# CoreCtrl.net
KiCad netlist of a schematic drawn in Altium Designer
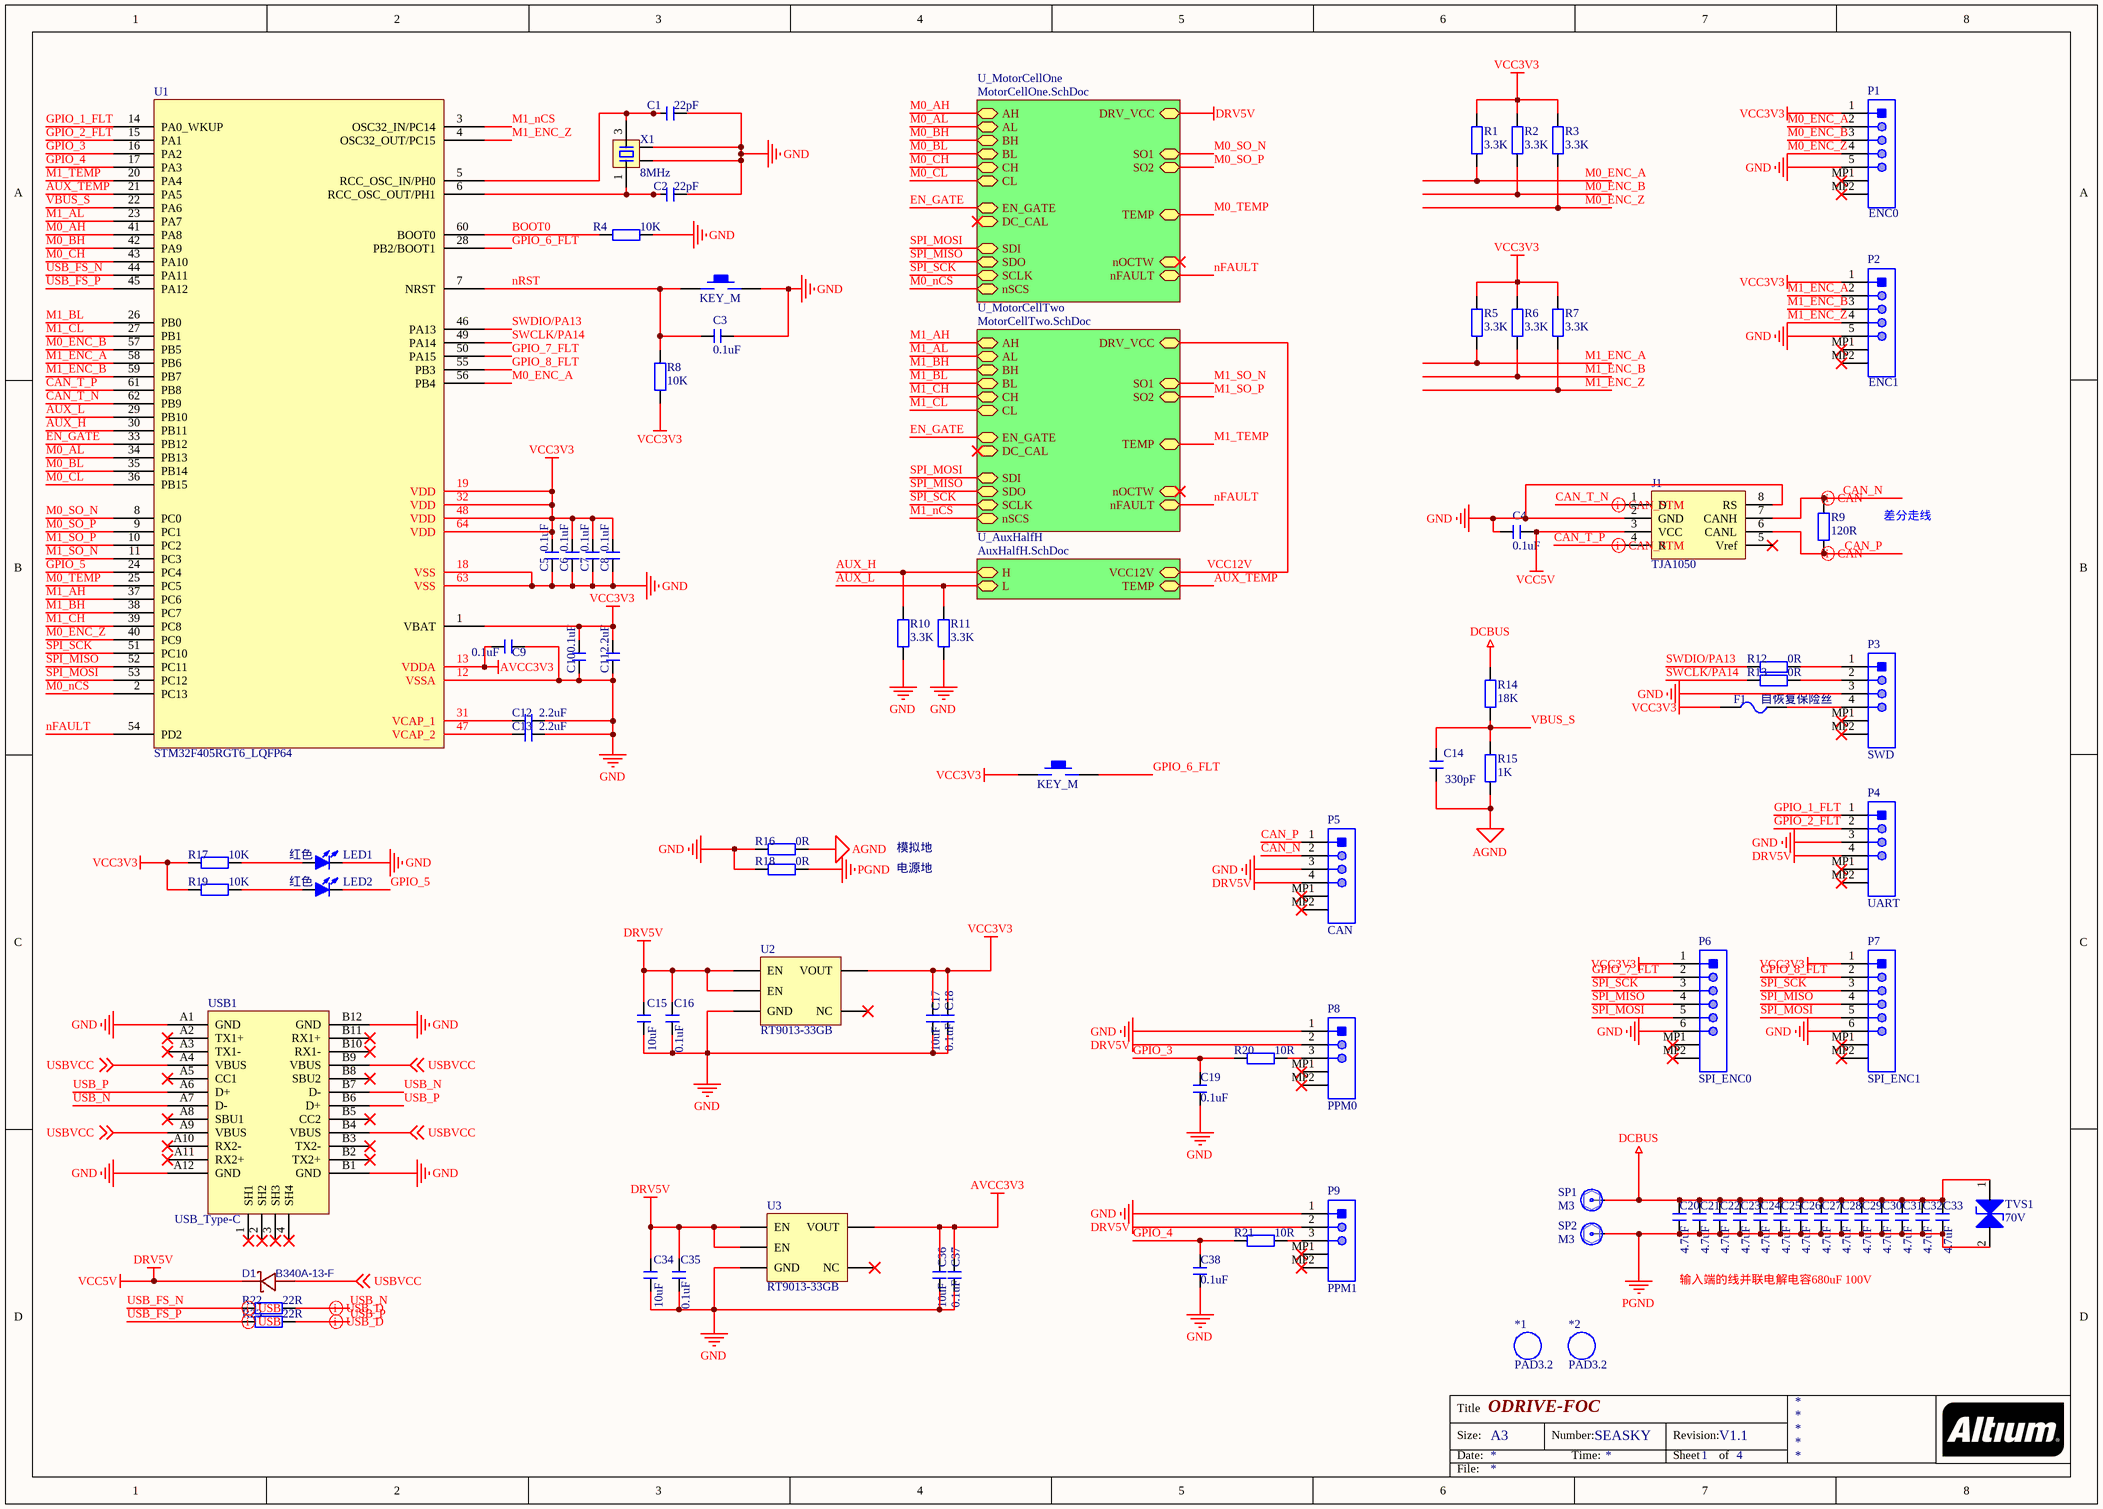
[diagram p0: CoreCtrl.SchDoc]

(export (version "E")
  (design (tool "Eeschema 10.0.6"))
  (components
    (comp (ref "*1") (value "PAD3.2") (footprint "PAD3.2") (libsource (lib "mx_pcb_library") (part "PAD3.2")))
    (comp (ref "*2") (value "PAD3.2") (footprint "PAD3.2") (libsource (lib "mx_pcb_library") (part "PAD3.2")))
    (comp (ref "C1")
      (value "22pF")
      (footprint "C 0603_L")
      (description "贴片电容")
      (libsource (lib "0.1 - 电阻-电容-电感") (part "C"))
    )
    (comp (ref "C2")
      (value "22pF")
      (footprint "C 0603_L")
      (description "贴片电容")
      (libsource (lib "0.1 - 电阻-电容-电感") (part "C"))
    )
    (comp (ref "C3")
      (value "0.1uF")
      (footprint "C 0603_L")
      (description "贴片电容")
      (libsource (lib "0.1 - 电阻-电容-电感") (part "C"))
    )
    (comp (ref "C4")
      (value "0.1uF")
      (footprint "C 0603_L")
      (description "贴片电容")
      (libsource (lib "0.1 - 电阻-电容-电感") (part "C"))
    )
    (comp (ref "C5")
      (value "0.1uF")
      (footprint "C 0603_L")
      (description "贴片电容")
      (libsource (lib "0.1 - 电阻-电容-电感") (part "C"))
    )
    (comp (ref "C6")
      (value "0.1uF")
      (footprint "C 0603_L")
      (description "贴片电容")
      (libsource (lib "0.1 - 电阻-电容-电感") (part "C"))
    )
    (comp (ref "C7")
      (value "0.1uF")
      (footprint "C 0603_L")
      (description "贴片电容")
      (libsource (lib "0.1 - 电阻-电容-电感") (part "C"))
    )
    (comp (ref "C8")
      (value "0.1uF")
      (footprint "C 0603_L")
      (description "贴片电容")
      (libsource (lib "0.1 - 电阻-电容-电感") (part "C"))
    )
    (comp (ref "C9")
      (value "0.1uF")
      (footprint "C 0603_L")
      (description "贴片电容")
      (libsource (lib "0.1 - 电阻-电容-电感") (part "C"))
    )
    (comp (ref "C10")
      (value "0.1uF")
      (footprint "C 0603_L")
      (description "贴片电容")
      (libsource (lib "0.1 - 电阻-电容-电感") (part "C"))
    )
    (comp (ref "C11")
      (value "2.2uF")
      (footprint "C 0603_L")
      (description "贴片电容")
      (libsource (lib "0.1 - 电阻-电容-电感") (part "C"))
    )
    (comp (ref "C12")
      (value "2.2uF")
      (footprint "C 0603_L")
      (description "贴片电容")
      (libsource (lib "0.1 - 电阻-电容-电感") (part "C"))
    )
    (comp (ref "C13")
      (value "2.2uF")
      (footprint "C 0603_L")
      (description "贴片电容")
      (libsource (lib "0.1 - 电阻-电容-电感") (part "C"))
    )
    (comp (ref "C14")
      (value "330pF")
      (footprint "C 0603_L")
      (description "贴片电容")
      (libsource (lib "0.1 - 电阻-电容-电感") (part "C"))
    )
    (comp (ref "C15")
      (value "10uF")
      (footprint "C 0805_L")
      (description "贴片电容")
      (libsource (lib "0.1 - 电阻-电容-电感") (part "C"))
    )
    (comp (ref "C16")
      (value "0.1uF")
      (footprint "C 0805_L")
      (description "贴片电容")
      (libsource (lib "0.1 - 电阻-电容-电感") (part "C"))
    )
    (comp (ref "C17")
      (value "10uF")
      (footprint "C 0805_L")
      (description "贴片电容")
      (libsource (lib "0.1 - 电阻-电容-电感") (part "C"))
    )
    (comp (ref "C18")
      (value "0.1uF")
      (footprint "C 0805_L")
      (description "贴片电容")
      (libsource (lib "0.1 - 电阻-电容-电感") (part "C"))
    )
    (comp (ref "C19")
      (value "0.1uF")
      (footprint "C 0603_L")
      (description "贴片电容")
      (libsource (lib "0.1 - 电阻-电容-电感") (part "C"))
    )
    (comp (ref "C20")
      (value "4.7uF")
      (footprint "C 1210_L")
      (description "贴片电容")
      (libsource (lib "0.1 - 电阻-电容-电感") (part "C"))
    )
    (comp (ref "C21")
      (value "4.7uF")
      (footprint "C 1210_L")
      (description "贴片电容")
      (libsource (lib "0.1 - 电阻-电容-电感") (part "C"))
    )
    (comp (ref "C22")
      (value "4.7uF")
      (footprint "C 1210_L")
      (description "贴片电容")
      (libsource (lib "0.1 - 电阻-电容-电感") (part "C"))
    )
    (comp (ref "C23")
      (value "4.7uF")
      (footprint "C 1210_L")
      (description "贴片电容")
      (libsource (lib "0.1 - 电阻-电容-电感") (part "C"))
    )
    (comp (ref "C24")
      (value "4.7uF")
      (footprint "C 1210_L")
      (description "贴片电容")
      (libsource (lib "0.1 - 电阻-电容-电感") (part "C"))
    )
    (comp (ref "C25")
      (value "4.7uF")
      (footprint "C 1210_L")
      (description "贴片电容")
      (libsource (lib "0.1 - 电阻-电容-电感") (part "C"))
    )
    (comp (ref "C26")
      (value "4.7uF")
      (footprint "C 1210_L")
      (description "贴片电容")
      (libsource (lib "0.1 - 电阻-电容-电感") (part "C"))
    )
    (comp (ref "C27")
      (value "4.7uF")
      (footprint "C 1210_L")
      (description "贴片电容")
      (libsource (lib "0.1 - 电阻-电容-电感") (part "C"))
    )
    (comp (ref "C28")
      (value "4.7uF")
      (footprint "C 1210_L")
      (description "贴片电容")
      (libsource (lib "0.1 - 电阻-电容-电感") (part "C"))
    )
    (comp (ref "C29")
      (value "4.7uF")
      (footprint "C 1210_L")
      (description "贴片电容")
      (libsource (lib "0.1 - 电阻-电容-电感") (part "C"))
    )
    (comp (ref "C30")
      (value "4.7uF")
      (footprint "C 1210_L")
      (description "贴片电容")
      (libsource (lib "0.1 - 电阻-电容-电感") (part "C"))
    )
    (comp (ref "C31")
      (value "4.7uF")
      (footprint "C 1210_L")
      (description "贴片电容")
      (libsource (lib "0.1 - 电阻-电容-电感") (part "C"))
    )
    (comp (ref "C32")
      (value "4.7uF")
      (footprint "C 1210_L")
      (description "贴片电容")
      (libsource (lib "0.1 - 电阻-电容-电感") (part "C"))
    )
    (comp (ref "C33")
      (value "4.7uF")
      (footprint "C 1210_L")
      (description "贴片电容")
      (libsource (lib "0.1 - 电阻-电容-电感") (part "C"))
    )
    (comp (ref "C34")
      (value "10uF")
      (footprint "C 0805_L")
      (description "贴片电容")
      (libsource (lib "0.1 - 电阻-电容-电感") (part "C"))
    )
    (comp (ref "C35")
      (value "0.1uF")
      (footprint "C 0805_L")
      (description "贴片电容")
      (libsource (lib "0.1 - 电阻-电容-电感") (part "C"))
    )
    (comp (ref "C36")
      (value "10uF")
      (footprint "C 0805_L")
      (description "贴片电容")
      (libsource (lib "0.1 - 电阻-电容-电感") (part "C"))
    )
    (comp (ref "C37")
      (value "0.1uF")
      (footprint "C 0805_L")
      (description "贴片电容")
      (libsource (lib "0.1 - 电阻-电容-电感") (part "C"))
    )
    (comp (ref "C38")
      (value "0.1uF")
      (footprint "C 0603_L")
      (description "贴片电容")
      (libsource (lib "0.1 - 电阻-电容-电感") (part "C"))
    )
    (comp (ref "D1")
      (value "B340A-13-F")
      (footprint "SMA_L4.4-W2.6-LS5.0-RD")
      (fields (field (name "BOM_SUPPLIER PART") "C85098"))
      (libsource (lib "mx_pcb_library") (part "B340A-13-F"))
    )
    (comp (ref "F1")
      (value "自恢复保险丝")
      (footprint "FU 0603")
      (description "贴片保险丝")
      (libsource (lib "2.0 - 保险丝-晶振-光耦") (part "FU"))
    )
    (comp (ref "J1")
      (value "TJA1050")
      (footprint "SOIC-8_150mil")
      (description "CAN芯片")
      (libsource (lib "mx_pcb_library") (part "TJA1050"))
    )
    (comp (ref "LED1")
      (value "红色")
      (footprint "LED 0805G")
      (description "贴片LED")
      (libsource (lib "0.3 - LED发光二极管") (part "LED-SMD"))
    )
    (comp (ref "LED2")
      (value "红色")
      (footprint "LED 0805G")
      (description "贴片LED")
      (libsource (lib "0.3 - LED发光二极管") (part "LED-SMD"))
    )
    (comp (ref "P1")
      (value "ENC0")
      (footprint "JST-SM05B-GHS-TB_V")
      (fields (field (name "MANUFACTURER") "JST"))
      (libsource (lib "JST GH connector") (part "SM05B-GHS-TB(LF)(SN)"))
    )
    (comp (ref "P2")
      (value "ENC1")
      (footprint "JST-SM05B-GHS-TB_V")
      (fields (field (name "MANUFACTURER") "JST"))
      (libsource (lib "JST GH connector") (part "SM05B-GHS-TB(LF)(SN)"))
    )
    (comp (ref "P3")
      (value "SWD")
      (footprint "JST-SM04B-GHS-TB_V")
      (fields (field (name "MANUFACTURER") "JST"))
      (libsource (lib "JST GH connector") (part "SM04B-GHS-TB(LF)(SN)"))
    )
    (comp (ref "P4")
      (value "UART")
      (footprint "JST-SM04B-GHS-TB_V")
      (fields (field (name "MANUFACTURER") "JST"))
      (libsource (lib "JST GH connector") (part "SM04B-GHS-TB(LF)(SN)"))
    )
    (comp (ref "P5")
      (value "CAN")
      (footprint "JST-SM04B-GHS-TB_V")
      (fields (field (name "MANUFACTURER") "JST"))
      (libsource (lib "JST GH connector") (part "SM04B-GHS-TB(LF)(SN)"))
    )
    (comp (ref "P6")
      (value "SPI_ENC0")
      (footprint "JST-SM06B-GHS-TB_V")
      (fields (field (name "MANUFACTURER") "JST"))
      (libsource (lib "JST GH connector") (part "SM06B-GHS-TB(LF)(SN)"))
    )
    (comp (ref "P7")
      (value "SPI_ENC1")
      (footprint "JST-BM06B-GHS-TBT_V")
      (fields (field (name "MANUFACTURER") "JST"))
      (libsource (lib "JST GH connector") (part "BM06B-GHS-TBT(LF)(SN)"))
    )
    (comp (ref "P8")
      (value "PPM0")
      (footprint "JST-SM03B-GHS-TB_V")
      (fields (field (name "MANUFACTURER") "JST"))
      (libsource (lib "JST GH connector") (part "SM03B-GHS-TB(LF)(SN)"))
    )
    (comp (ref "P9")
      (value "PPM1")
      (footprint "JST-SM03B-GHS-TB_V")
      (fields (field (name "MANUFACTURER") "JST"))
      (libsource (lib "JST GH connector") (part "SM03B-GHS-TB(LF)(SN)"))
    )
    (comp (ref "R1")
      (value "3.3K")
      (footprint "R 0603_L")
      (description "贴片电阻")
      (libsource (lib "0.1 - 电阻-电容-电感") (part "R"))
    )
    (comp (ref "R2")
      (value "3.3K")
      (footprint "R 0603_L")
      (description "贴片电阻")
      (libsource (lib "0.1 - 电阻-电容-电感") (part "R"))
    )
    (comp (ref "R3")
      (value "3.3K")
      (footprint "R 0603_L")
      (description "贴片电阻")
      (libsource (lib "0.1 - 电阻-电容-电感") (part "R"))
    )
    (comp (ref "R4")
      (value "10K")
      (footprint "R 0603_L")
      (description "贴片电阻")
      (libsource (lib "0.1 - 电阻-电容-电感") (part "R"))
    )
    (comp (ref "R5")
      (value "3.3K")
      (footprint "R 0603_L")
      (description "贴片电阻")
      (libsource (lib "0.1 - 电阻-电容-电感") (part "R"))
    )
    (comp (ref "R6")
      (value "3.3K")
      (footprint "R 0603_L")
      (description "贴片电阻")
      (libsource (lib "0.1 - 电阻-电容-电感") (part "R"))
    )
    (comp (ref "R7")
      (value "3.3K")
      (footprint "R 0603_L")
      (description "贴片电阻")
      (libsource (lib "0.1 - 电阻-电容-电感") (part "R"))
    )
    (comp (ref "R8")
      (value "10K")
      (footprint "R 0603_L")
      (description "贴片电阻")
      (libsource (lib "0.1 - 电阻-电容-电感") (part "R"))
    )
    (comp (ref "R9")
      (value "120R")
      (footprint "R 0603_L")
      (description "贴片电阻")
      (libsource (lib "0.1 - 电阻-电容-电感") (part "R"))
    )
    (comp (ref "R10")
      (value "3.3K")
      (footprint "R 0603_L")
      (description "贴片电阻")
      (libsource (lib "0.1 - 电阻-电容-电感") (part "R"))
    )
    (comp (ref "R11")
      (value "3.3K")
      (footprint "R 0603_L")
      (description "贴片电阻")
      (libsource (lib "0.1 - 电阻-电容-电感") (part "R"))
    )
    (comp (ref "R12")
      (value "0R")
      (footprint "R 0603_L")
      (description "贴片电阻")
      (libsource (lib "0.1 - 电阻-电容-电感") (part "R"))
    )
    (comp (ref "R13")
      (value "0R")
      (footprint "R 0603_L")
      (description "贴片电阻")
      (libsource (lib "0.1 - 电阻-电容-电感") (part "R"))
    )
    (comp (ref "R14")
      (value "18K")
      (footprint "R 0603_L")
      (description "贴片电阻")
      (libsource (lib "0.1 - 电阻-电容-电感") (part "R"))
    )
    (comp (ref "R15")
      (value "1K")
      (footprint "R 0603_L")
      (description "贴片电阻")
      (libsource (lib "0.1 - 电阻-电容-电感") (part "R"))
    )
    (comp (ref "R16")
      (value "0R")
      (footprint "R 0603_L")
      (description "贴片电阻")
      (libsource (lib "0.1 - 电阻-电容-电感") (part "R"))
    )
    (comp (ref "R17")
      (value "10K")
      (footprint "R 0603_L")
      (description "贴片电阻")
      (libsource (lib "0.1 - 电阻-电容-电感") (part "R"))
    )
    (comp (ref "R18")
      (value "0R")
      (footprint "R 0603_L")
      (description "贴片电阻")
      (libsource (lib "0.1 - 电阻-电容-电感") (part "R"))
    )
    (comp (ref "R19")
      (value "10K")
      (footprint "R 0603_L")
      (description "贴片电阻")
      (libsource (lib "0.1 - 电阻-电容-电感") (part "R"))
    )
    (comp (ref "R20")
      (value "10R")
      (footprint "R 0603_L")
      (description "贴片电阻")
      (libsource (lib "0.1 - 电阻-电容-电感") (part "R"))
    )
    (comp (ref "R21")
      (value "10R")
      (footprint "R 0603_L")
      (description "贴片电阻")
      (libsource (lib "0.1 - 电阻-电容-电感") (part "R"))
    )
    (comp (ref "R22")
      (value "22R")
      (footprint "R 0603_L")
      (description "贴片电阻")
      (libsource (lib "0.1 - 电阻-电容-电感") (part "R"))
    )
    (comp (ref "R23")
      (value "22R")
      (footprint "R 0603_L")
      (description "贴片电阻")
      (libsource (lib "0.1 - 电阻-电容-电感") (part "R"))
    )
    (comp (ref "RST1")
      (value "KEY_M")
      (footprint "SMD-3.2*4.2")
      (libsource (lib "mx_pcb_library") (part "KEY_M"))
    )
    (comp (ref "RST2")
      (value "KEY_M")
      (footprint "SMD-3.2*4.2")
      (libsource (lib "mx_pcb_library") (part "KEY_M"))
    )
    (comp (ref "SP1")
      (value "M3")
      (footprint "PAD1.5")
      (description "铜柱")
      (libsource (lib "mx_pcb_library") (part "固定焊盘"))
    )
    (comp (ref "SP2")
      (value "M3")
      (footprint "PAD1.5")
      (description "铜柱")
      (libsource (lib "mx_pcb_library") (part "固定焊盘"))
    )
    (comp (ref "TVS1")
      (value "70V")
      (footprint "SMA(DO-214AC)")
      (libsource (lib "mx_pcb_library") (part "SMAJ28CA"))
    )
    (comp (ref "U1")
      (value "STM32F405RGT6_LQFP64")
      (footprint "LQFP-64_10X10X05P")
      (libsource (lib "mx_pcb_library") (part "STM32F405RGT6_LQFP64"))
    )
    (comp (ref "U2")
      (value "RT9013-33GB")
      (footprint "SOT23-5M")
      (libsource (lib "mx_pcb_library") (part "RT9013-33GB"))
    )
    (comp (ref "U3")
      (value "RT9013-33GB")
      (footprint "SOT23-5M")
      (libsource (lib "mx_pcb_library") (part "RT9013-33GB"))
    )
    (comp (ref "USB1")
      (value "USB_Type-C")
      (footprint "Type-C-TOP")
      (libsource (lib "mx_pcb_library") (part "USB_Type-C"))
    )
    (comp (ref "X1")
      (value "8MHz")
      (footprint "OSC 3225-4P")
      (description "4脚无源晶振")
      (libsource (lib "2.0 - 保险丝-晶振-光耦") (part "XTAL-4P"))
    )
  )
  (nets
    (net (code "1") (name "/AUX_H") (class "Default")
      (node (ref "R10") (pin "1") (pinfunction "1_1") (pintype "passive"))
      (node (ref "U1") (pin "30") (pinfunction "PB11_30") (pintype "passive"))
    )
    (net (code "2") (name "/AUX_L") (class "Default")
      (node (ref "R11") (pin "1") (pinfunction "1_1") (pintype "passive"))
      (node (ref "U1") (pin "29") (pinfunction "PB10_29") (pintype "passive"))
    )
    (net (code "3") (name "/AUX_TEMP") (class "Default")
      (node (ref "U1") (pin "21") (pinfunction "PA5_21") (pintype "passive"))
    )
    (net (code "4") (name "/BOOT0") (class "Default")
      (node (ref "R4") (pin "2") (pinfunction "2_2") (pintype "passive"))
      (node (ref "U1") (pin "60") (pinfunction "BOOT0_60") (pintype "passive"))
    )
    (net (code "5") (name "/CAN_N") (class "Default")
      (node (ref "J1") (pin "7") (pinfunction "CANH_7") (pintype "passive"))
      (node (ref "P5") (pin "2") (pinfunction "2_2") (pintype "passive"))
      (node (ref "R9") (pin "1") (pinfunction "1_1") (pintype "passive"))
    )
    (net (code "6") (name "/CAN_P") (class "Default")
      (node (ref "J1") (pin "6") (pinfunction "CANL_6") (pintype "passive"))
      (node (ref "P5") (pin "1") (pinfunction "1_1") (pintype "passive"))
      (node (ref "R9") (pin "2") (pinfunction "2_2") (pintype "passive"))
    )
    (net (code "7") (name "/CAN_T_N") (class "Default")
      (node (ref "J1") (pin "1") (pinfunction "D_1") (pintype "passive"))
      (node (ref "U1") (pin "62") (pinfunction "PB9_62") (pintype "passive"))
    )
    (net (code "8") (name "/CAN_T_P") (class "Default")
      (node (ref "J1") (pin "4") (pinfunction "R_4") (pintype "passive"))
      (node (ref "U1") (pin "61") (pinfunction "PB8_61") (pintype "passive"))
    )
    (net (code "11") (name "/EN_GATE") (class "Default")
      (node (ref "U1") (pin "33") (pinfunction "PB12_33") (pintype "passive"))
    )
    (net (code "12") (name "/GPIO_1_FLT") (class "Default")
      (node (ref "P4") (pin "1") (pinfunction "1_1") (pintype "passive"))
      (node (ref "U1") (pin "14") (pinfunction "PA0_WKUP_14") (pintype "passive"))
    )
    (net (code "13") (name "/GPIO_2_FLT") (class "Default")
      (node (ref "P4") (pin "2") (pinfunction "2_2") (pintype "passive"))
      (node (ref "U1") (pin "15") (pinfunction "PA1_15") (pintype "passive"))
    )
    (net (code "14") (name "/GPIO_3") (class "Default")
      (node (ref "C19") (pin "2") (pinfunction "2_2") (pintype "passive"))
      (node (ref "R20") (pin "1") (pinfunction "1_1") (pintype "passive"))
      (node (ref "U1") (pin "16") (pinfunction "PA2_16") (pintype "passive"))
    )
    (net (code "15") (name "/GPIO_4") (class "Default")
      (node (ref "C38") (pin "2") (pinfunction "2_2") (pintype "passive"))
      (node (ref "R21") (pin "1") (pinfunction "1_1") (pintype "passive"))
      (node (ref "U1") (pin "17") (pinfunction "PA3_17") (pintype "passive"))
    )
    (net (code "16") (name "/GPIO_5") (class "Default")
      (node (ref "LED2") (pin "2") (pinfunction "K_2") (pintype "passive"))
      (node (ref "U1") (pin "24") (pinfunction "PC4_24") (pintype "passive"))
    )
    (net (code "17") (name "/GPIO_6_FLT") (class "Default")
      (node (ref "RST2") (pin "2") (pinfunction "2_2") (pintype "passive"))
      (node (ref "U1") (pin "28") (pinfunction "PB2/BOOT1_28") (pintype "passive"))
    )
    (net (code "18") (name "/GPIO_7_FLT") (class "Default")
      (node (ref "P6") (pin "2") (pinfunction "2_2") (pintype "passive"))
      (node (ref "U1") (pin "50") (pinfunction "PA15_50") (pintype "passive"))
    )
    (net (code "19") (name "/GPIO_8_FLT") (class "Default")
      (node (ref "P7") (pin "2") (pinfunction "2_2") (pintype "passive"))
      (node (ref "U1") (pin "55") (pinfunction "PB3_55") (pintype "passive"))
    )
    (net (code "20") (name "/M0_AH") (class "Default")
      (node (ref "U1") (pin "41") (pinfunction "PA8_41") (pintype "passive"))
    )
    (net (code "21") (name "/M0_AL") (class "Default")
      (node (ref "U1") (pin "34") (pinfunction "PB13_34") (pintype "passive"))
    )
    (net (code "22") (name "/M0_BH") (class "Default")
      (node (ref "U1") (pin "42") (pinfunction "PA9_42") (pintype "passive"))
    )
    (net (code "23") (name "/M0_BL") (class "Default")
      (node (ref "U1") (pin "35") (pinfunction "PB14_35") (pintype "passive"))
    )
    (net (code "24") (name "/M0_CH") (class "Default")
      (node (ref "U1") (pin "43") (pinfunction "PA10_43") (pintype "passive"))
    )
    (net (code "25") (name "/M0_CL") (class "Default")
      (node (ref "U1") (pin "36") (pinfunction "PB15_36") (pintype "passive"))
    )
    (net (code "26") (name "/M0_ENC_A") (class "Default")
      (node (ref "P1") (pin "2") (pinfunction "2_2") (pintype "passive"))
      (node (ref "R1") (pin "2") (pinfunction "2_2") (pintype "passive"))
      (node (ref "U1") (pin "56") (pinfunction "PB4_56") (pintype "passive"))
    )
    (net (code "27") (name "/M0_ENC_B") (class "Default")
      (node (ref "P1") (pin "3") (pinfunction "3_3") (pintype "passive"))
      (node (ref "R2") (pin "2") (pinfunction "2_2") (pintype "passive"))
      (node (ref "U1") (pin "57") (pinfunction "PB5_57") (pintype "passive"))
    )
    (net (code "28") (name "/M0_ENC_Z") (class "Default")
      (node (ref "P1") (pin "4") (pinfunction "4_4") (pintype "passive"))
      (node (ref "R3") (pin "2") (pinfunction "2_2") (pintype "passive"))
      (node (ref "U1") (pin "40") (pinfunction "PC9_40") (pintype "passive"))
    )
    (net (code "29") (name "/M0_SO_N") (class "Default")
      (node (ref "U1") (pin "8") (pinfunction "PC0_8") (pintype "passive"))
    )
    (net (code "30") (name "/M0_SO_P") (class "Default")
      (node (ref "U1") (pin "9") (pinfunction "PC1_9") (pintype "passive"))
    )
    (net (code "31") (name "/M0_TEMP") (class "Default")
      (node (ref "U1") (pin "25") (pinfunction "PC5_25") (pintype "passive"))
    )
    (net (code "32") (name "/M0_nCS") (class "Default")
      (node (ref "U1") (pin "2") (pinfunction "PC13_2") (pintype "passive"))
    )
    (net (code "33") (name "/M1_AH") (class "Default")
      (node (ref "U1") (pin "37") (pinfunction "PC6_37") (pintype "passive"))
    )
    (net (code "34") (name "/M1_AL") (class "Default")
      (node (ref "U1") (pin "23") (pinfunction "PA7_23") (pintype "passive"))
    )
    (net (code "35") (name "/M1_BH") (class "Default")
      (node (ref "U1") (pin "38") (pinfunction "PC7_38") (pintype "passive"))
    )
    (net (code "36") (name "/M1_BL") (class "Default")
      (node (ref "U1") (pin "26") (pinfunction "PB0_26") (pintype "passive"))
    )
    (net (code "37") (name "/M1_CH") (class "Default")
      (node (ref "U1") (pin "39") (pinfunction "PC8_39") (pintype "passive"))
    )
    (net (code "38") (name "/M1_CL") (class "Default")
      (node (ref "U1") (pin "27") (pinfunction "PB1_27") (pintype "passive"))
    )
    (net (code "39") (name "/M1_ENC_A") (class "Default")
      (node (ref "P2") (pin "2") (pinfunction "2_2") (pintype "passive"))
      (node (ref "R5") (pin "2") (pinfunction "2_2") (pintype "passive"))
      (node (ref "U1") (pin "58") (pinfunction "PB6_58") (pintype "passive"))
    )
    (net (code "40") (name "/M1_ENC_B") (class "Default")
      (node (ref "P2") (pin "3") (pinfunction "3_3") (pintype "passive"))
      (node (ref "R6") (pin "2") (pinfunction "2_2") (pintype "passive"))
      (node (ref "U1") (pin "59") (pinfunction "PB7_59") (pintype "passive"))
    )
    (net (code "41") (name "/M1_ENC_Z") (class "Default")
      (node (ref "P2") (pin "4") (pinfunction "4_4") (pintype "passive"))
      (node (ref "R7") (pin "2") (pinfunction "2_2") (pintype "passive"))
      (node (ref "U1") (pin "4") (pinfunction "OSC32_OUT/PC15_4") (pintype "passive"))
    )
    (net (code "42") (name "/M1_SO_N") (class "Default")
      (node (ref "U1") (pin "11") (pinfunction "PC3_11") (pintype "passive"))
    )
    (net (code "43") (name "/M1_SO_P") (class "Default")
      (node (ref "U1") (pin "10") (pinfunction "PC2_10") (pintype "passive"))
    )
    (net (code "44") (name "/M1_TEMP") (class "Default")
      (node (ref "U1") (pin "20") (pinfunction "PA4_20") (pintype "passive"))
    )
    (net (code "45") (name "/M1_nCS") (class "Default")
      (node (ref "U1") (pin "3") (pinfunction "OSC32_IN/PC14_3") (pintype "passive"))
    )
    (net (code "46") (name "/SPI_MISO") (class "Default")
      (node (ref "P6") (pin "4") (pinfunction "4_4") (pintype "passive"))
      (node (ref "P7") (pin "4") (pinfunction "4_4") (pintype "passive"))
      (node (ref "U1") (pin "52") (pinfunction "PC11_52") (pintype "passive"))
    )
    (net (code "47") (name "/SPI_MOSI") (class "Default")
      (node (ref "P6") (pin "5") (pinfunction "5_5") (pintype "passive"))
      (node (ref "P7") (pin "5") (pinfunction "5_5") (pintype "passive"))
      (node (ref "U1") (pin "53") (pinfunction "PC12_53") (pintype "passive"))
    )
    (net (code "48") (name "/SPI_SCK") (class "Default")
      (node (ref "P6") (pin "3") (pinfunction "3_3") (pintype "passive"))
      (node (ref "P7") (pin "3") (pinfunction "3_3") (pintype "passive"))
      (node (ref "U1") (pin "51") (pinfunction "PC10_51") (pintype "passive"))
    )
    (net (code "49") (name "/SWCLK{slash}PA14") (class "Default")
      (node (ref "R13") (pin "2") (pinfunction "2_2") (pintype "passive"))
      (node (ref "U1") (pin "49") (pinfunction "PA14_49") (pintype "passive"))
    )
    (net (code "50") (name "/SWDIO{slash}PA13") (class "Default")
      (node (ref "R12") (pin "2") (pinfunction "2_2") (pintype "passive"))
      (node (ref "U1") (pin "46") (pinfunction "PA13_46") (pintype "passive"))
    )
    (net (code "51") (name "/USB_FS_N") (class "Default")
      (node (ref "R22") (pin "1") (pinfunction "1_1") (pintype "passive"))
      (node (ref "U1") (pin "44") (pinfunction "PA11_44") (pintype "passive"))
    )
    (net (code "52") (name "/USB_FS_P") (class "Default")
      (node (ref "R23") (pin "1") (pinfunction "1_1") (pintype "passive"))
      (node (ref "U1") (pin "45") (pinfunction "PA12_45") (pintype "passive"))
    )
    (net (code "53") (name "/USB_N") (class "Default")
      (node (ref "R22") (pin "2") (pinfunction "2_2") (pintype "passive"))
      (node (ref "USB1") (pin "A7") (pinfunction "D-_A7") (pintype "passive"))
      (node (ref "USB1") (pin "B7") (pinfunction "D-_B7") (pintype "passive"))
    )
    (net (code "54") (name "/USB_P") (class "Default")
      (node (ref "R23") (pin "2") (pinfunction "2_2") (pintype "passive"))
      (node (ref "USB1") (pin "A6") (pinfunction "D+_A6") (pintype "passive"))
      (node (ref "USB1") (pin "B6") (pinfunction "D+_B6") (pintype "passive"))
    )
    (net (code "55") (name "/VBUS_S") (class "Default")
      (node (ref "C14") (pin "1") (pinfunction "1_1") (pintype "passive"))
      (node (ref "R14") (pin "2") (pinfunction "2_2") (pintype "passive"))
      (node (ref "R15") (pin "1") (pinfunction "1_1") (pintype "passive"))
      (node (ref "U1") (pin "22") (pinfunction "PA6_22") (pintype "passive"))
    )
    (net (code "57") (name "/nFAULT") (class "Default")
      (node (ref "U1") (pin "54") (pinfunction "PD2_54") (pintype "passive"))
    )
    (net (code "60") (name "/nRST") (class "Default")
      (node (ref "C3") (pin "2") (pinfunction "2_2") (pintype "passive"))
      (node (ref "R8") (pin "2") (pinfunction "2_2") (pintype "passive"))
      (node (ref "RST1") (pin "1") (pinfunction "1_1") (pintype "passive"))
      (node (ref "U1") (pin "7") (pinfunction "NRST_7") (pintype "passive"))
    )
    (net (code "61") (name "AGND") (class "Default")
      (node (ref "C14") (pin "2") (pinfunction "2_2") (pintype "passive"))
      (node (ref "R15") (pin "2") (pinfunction "2_2") (pintype "passive"))
      (node (ref "R16") (pin "1") (pinfunction "1_1") (pintype "passive"))
    )
    (net (code "62") (name "AVCC3V3") (class "Default")
      (node (ref "C36") (pin "2") (pinfunction "2_2") (pintype "passive"))
      (node (ref "C37") (pin "2") (pinfunction "2_2") (pintype "passive"))
      (node (ref "C9") (pin "2") (pinfunction "2_2") (pintype "passive"))
      (node (ref "U1") (pin "13") (pinfunction "VDDA_13") (pintype "passive"))
      (node (ref "U3") (pin "5") (pinfunction "VOUT_5") (pintype "passive"))
    )
    (net (code "63") (name "DCBUS") (class "Default")
      (node (ref "C20") (pin "2") (pinfunction "2_2") (pintype "passive"))
      (node (ref "C21") (pin "2") (pinfunction "2_2") (pintype "passive"))
      (node (ref "C22") (pin "2") (pinfunction "2_2") (pintype "passive"))
      (node (ref "C23") (pin "2") (pinfunction "2_2") (pintype "passive"))
      (node (ref "C24") (pin "2") (pinfunction "2_2") (pintype "passive"))
      (node (ref "C25") (pin "2") (pinfunction "2_2") (pintype "passive"))
      (node (ref "C26") (pin "2") (pinfunction "2_2") (pintype "passive"))
      (node (ref "C27") (pin "2") (pinfunction "2_2") (pintype "passive"))
      (node (ref "C28") (pin "2") (pinfunction "2_2") (pintype "passive"))
      (node (ref "C29") (pin "2") (pinfunction "2_2") (pintype "passive"))
      (node (ref "C30") (pin "2") (pinfunction "2_2") (pintype "passive"))
      (node (ref "C31") (pin "2") (pinfunction "2_2") (pintype "passive"))
      (node (ref "C32") (pin "2") (pinfunction "2_2") (pintype "passive"))
      (node (ref "C33") (pin "2") (pinfunction "2_2") (pintype "passive"))
      (node (ref "R14") (pin "1") (pinfunction "1_1") (pintype "passive"))
      (node (ref "SP1") (pin "0") (pinfunction "1_0") (pintype "passive"))
      (node (ref "TVS1") (pin "1") (pinfunction "1_1") (pintype "passive"))
    )
    (net (code "64") (name "DRV5V") (class "Default")
      (node (ref "C15") (pin "2") (pinfunction "2_2") (pintype "passive"))
      (node (ref "C16") (pin "2") (pinfunction "2_2") (pintype "passive"))
      (node (ref "C34") (pin "2") (pinfunction "2_2") (pintype "passive"))
      (node (ref "C35") (pin "2") (pinfunction "2_2") (pintype "passive"))
      (node (ref "C4") (pin "1") (pinfunction "1_1") (pintype "passive"))
      (node (ref "D1") (pin "1") (pinfunction "K_1") (pintype "passive"))
      (node (ref "J1") (pin "3") (pinfunction "VCC_3") (pintype "passive"))
      (node (ref "P4") (pin "4") (pinfunction "4_4") (pintype "passive"))
      (node (ref "P5") (pin "4") (pinfunction "4_4") (pintype "passive"))
      (node (ref "P8") (pin "2") (pinfunction "2_2") (pintype "passive"))
      (node (ref "P9") (pin "2") (pinfunction "2_2") (pintype "passive"))
      (node (ref "U2") (pin "1") (pinfunction "EN_1") (pintype "passive"))
      (node (ref "U2") (pin "3") (pinfunction "EN_3") (pintype "passive"))
      (node (ref "U3") (pin "1") (pinfunction "EN_1") (pintype "passive"))
      (node (ref "U3") (pin "3") (pinfunction "EN_3") (pintype "passive"))
    )
    (net (code "65") (name "GND") (class "Default")
      (node (ref "C1") (pin "2") (pinfunction "2_2") (pintype "passive"))
      (node (ref "C10") (pin "1") (pinfunction "1_1") (pintype "passive"))
      (node (ref "C11") (pin "1") (pinfunction "1_1") (pintype "passive"))
      (node (ref "C12") (pin "2") (pinfunction "2_2") (pintype "passive"))
      (node (ref "C13") (pin "2") (pinfunction "2_2") (pintype "passive"))
      (node (ref "C15") (pin "1") (pinfunction "1_1") (pintype "passive"))
      (node (ref "C16") (pin "1") (pinfunction "1_1") (pintype "passive"))
      (node (ref "C17") (pin "1") (pinfunction "1_1") (pintype "passive"))
      (node (ref "C18") (pin "1") (pinfunction "1_1") (pintype "passive"))
      (node (ref "C19") (pin "1") (pinfunction "1_1") (pintype "passive"))
      (node (ref "C2") (pin "2") (pinfunction "2_2") (pintype "passive"))
      (node (ref "C3") (pin "1") (pinfunction "1_1") (pintype "passive"))
      (node (ref "C34") (pin "1") (pinfunction "1_1") (pintype "passive"))
      (node (ref "C35") (pin "1") (pinfunction "1_1") (pintype "passive"))
      (node (ref "C36") (pin "1") (pinfunction "1_1") (pintype "passive"))
      (node (ref "C37") (pin "1") (pinfunction "1_1") (pintype "passive"))
      (node (ref "C38") (pin "1") (pinfunction "1_1") (pintype "passive"))
      (node (ref "C4") (pin "2") (pinfunction "2_2") (pintype "passive"))
      (node (ref "C5") (pin "1") (pinfunction "1_1") (pintype "passive"))
      (node (ref "C6") (pin "1") (pinfunction "1_1") (pintype "passive"))
      (node (ref "C7") (pin "1") (pinfunction "1_1") (pintype "passive"))
      (node (ref "C8") (pin "1") (pinfunction "1_1") (pintype "passive"))
      (node (ref "C9") (pin "1") (pinfunction "1_1") (pintype "passive"))
      (node (ref "J1") (pin "2") (pinfunction "GND_2") (pintype "passive"))
      (node (ref "J1") (pin "8") (pinfunction "RS_8") (pintype "passive"))
      (node (ref "LED1") (pin "2") (pinfunction "K_2") (pintype "passive"))
      (node (ref "P1") (pin "5") (pinfunction "5_5") (pintype "passive"))
      (node (ref "P2") (pin "5") (pinfunction "5_5") (pintype "passive"))
      (node (ref "P3") (pin "3") (pinfunction "3_3") (pintype "passive"))
      (node (ref "P4") (pin "3") (pinfunction "3_3") (pintype "passive"))
      (node (ref "P5") (pin "3") (pinfunction "3_3") (pintype "passive"))
      (node (ref "P6") (pin "6") (pinfunction "6_6") (pintype "passive"))
      (node (ref "P7") (pin "6") (pinfunction "6_6") (pintype "passive"))
      (node (ref "P8") (pin "1") (pinfunction "1_1") (pintype "passive"))
      (node (ref "P9") (pin "1") (pinfunction "1_1") (pintype "passive"))
      (node (ref "R10") (pin "2") (pinfunction "2_2") (pintype "passive"))
      (node (ref "R11") (pin "2") (pinfunction "2_2") (pintype "passive"))
      (node (ref "R16") (pin "2") (pinfunction "2_2") (pintype "passive"))
      (node (ref "R18") (pin "2") (pinfunction "2_2") (pintype "passive"))
      (node (ref "R4") (pin "1") (pinfunction "1_1") (pintype "passive"))
      (node (ref "RST1") (pin "2") (pinfunction "2_2") (pintype "passive"))
      (node (ref "U1") (pin "12") (pinfunction "VSSA_12") (pintype "passive"))
      (node (ref "U1") (pin "18") (pinfunction "VSS_18") (pintype "passive"))
      (node (ref "U1") (pin "63") (pinfunction "VSS_63") (pintype "passive"))
      (node (ref "U2") (pin "2") (pinfunction "GND_2") (pintype "passive"))
      (node (ref "U3") (pin "2") (pinfunction "GND_2") (pintype "passive"))
      (node (ref "USB1") (pin "A1") (pinfunction "GND_A1") (pintype "passive"))
      (node (ref "USB1") (pin "A12") (pinfunction "GND_A12") (pintype "passive"))
      (node (ref "USB1") (pin "B1") (pinfunction "GND_B1") (pintype "passive"))
      (node (ref "USB1") (pin "B12") (pinfunction "GND_B12") (pintype "passive"))
      (node (ref "X1") (pin "2") (pinfunction "2_2") (pintype "passive"))
      (node (ref "X1") (pin "4") (pinfunction "4_4") (pintype "passive"))
    )
    (net (code "66") (name "Net-(F1-Pad1)") (class "Default")
      (node (ref "F1") (pin "1") (pinfunction "1_1") (pintype "passive"))
      (node (ref "P3") (pin "4") (pinfunction "4_4") (pintype "passive"))
    )
    (net (code "67") (name "Net-(LED1-A)") (class "Default")
      (node (ref "LED1") (pin "1") (pinfunction "A_1") (pintype "passive"))
      (node (ref "R17") (pin "2") (pinfunction "2_2") (pintype "passive"))
    )
    (net (code "68") (name "Net-(LED2-A)") (class "Default")
      (node (ref "LED2") (pin "1") (pinfunction "A_1") (pintype "passive"))
      (node (ref "R19") (pin "2") (pinfunction "2_2") (pintype "passive"))
    )
    (net (code "69") (name "Net-(P3-Pad1)") (class "Default")
      (node (ref "P3") (pin "1") (pinfunction "1_1") (pintype "passive"))
      (node (ref "R12") (pin "1") (pinfunction "1_1") (pintype "passive"))
    )
    (net (code "70") (name "Net-(P3-Pad2)") (class "Default")
      (node (ref "P3") (pin "2") (pinfunction "2_2") (pintype "passive"))
      (node (ref "R13") (pin "1") (pinfunction "1_1") (pintype "passive"))
    )
    (net (code "71") (name "Net-(P8-Pad3)") (class "Default")
      (node (ref "P8") (pin "3") (pinfunction "3_3") (pintype "passive"))
      (node (ref "R20") (pin "2") (pinfunction "2_2") (pintype "passive"))
    )
    (net (code "72") (name "Net-(P9-Pad3)") (class "Default")
      (node (ref "P9") (pin "3") (pinfunction "3_3") (pintype "passive"))
      (node (ref "R21") (pin "2") (pinfunction "2_2") (pintype "passive"))
    )
    (net (code "73") (name "Net-(U1-RCC_OSC_IN{slash}PH0)") (class "Default")
      (node (ref "C1") (pin "1") (pinfunction "1_1") (pintype "passive"))
      (node (ref "U1") (pin "5") (pinfunction "RCC_OSC_IN/PH0_5") (pintype "passive"))
      (node (ref "X1") (pin "3") (pinfunction "3_3") (pintype "passive"))
    )
    (net (code "74") (name "Net-(U1-RCC_OSC_OUT{slash}PH1)") (class "Default")
      (node (ref "C2") (pin "1") (pinfunction "1_1") (pintype "passive"))
      (node (ref "U1") (pin "6") (pinfunction "RCC_OSC_OUT/PH1_6") (pintype "passive"))
      (node (ref "X1") (pin "1") (pinfunction "1_1") (pintype "passive"))
    )
    (net (code "75") (name "Net-(U1-VCAP_1)") (class "Default")
      (node (ref "C12") (pin "1") (pinfunction "1_1") (pintype "passive"))
      (node (ref "U1") (pin "31") (pinfunction "VCAP_1_31") (pintype "passive"))
    )
    (net (code "76") (name "Net-(U1-VCAP_2)") (class "Default")
      (node (ref "C13") (pin "1") (pinfunction "1_1") (pintype "passive"))
      (node (ref "U1") (pin "47") (pinfunction "VCAP_2_47") (pintype "passive"))
    )
    (net (code "77") (name "PGND") (class "Default")
      (node (ref "C20") (pin "1") (pinfunction "1_1") (pintype "passive"))
      (node (ref "C21") (pin "1") (pinfunction "1_1") (pintype "passive"))
      (node (ref "C22") (pin "1") (pinfunction "1_1") (pintype "passive"))
      (node (ref "C23") (pin "1") (pinfunction "1_1") (pintype "passive"))
      (node (ref "C24") (pin "1") (pinfunction "1_1") (pintype "passive"))
      (node (ref "C25") (pin "1") (pinfunction "1_1") (pintype "passive"))
      (node (ref "C26") (pin "1") (pinfunction "1_1") (pintype "passive"))
      (node (ref "C27") (pin "1") (pinfunction "1_1") (pintype "passive"))
      (node (ref "C28") (pin "1") (pinfunction "1_1") (pintype "passive"))
      (node (ref "C29") (pin "1") (pinfunction "1_1") (pintype "passive"))
      (node (ref "C30") (pin "1") (pinfunction "1_1") (pintype "passive"))
      (node (ref "C31") (pin "1") (pinfunction "1_1") (pintype "passive"))
      (node (ref "C32") (pin "1") (pinfunction "1_1") (pintype "passive"))
      (node (ref "C33") (pin "1") (pinfunction "1_1") (pintype "passive"))
      (node (ref "R18") (pin "1") (pinfunction "1_1") (pintype "passive"))
      (node (ref "SP2") (pin "0") (pinfunction "1_0") (pintype "passive"))
      (node (ref "TVS1") (pin "2") (pinfunction "2_2") (pintype "passive"))
    )
    (net (code "78") (name "USBVCC") (class "Default")
      (node (ref "D1") (pin "2") (pinfunction "A_2") (pintype "passive"))
      (node (ref "USB1") (pin "A4") (pinfunction "VBUS_A4") (pintype "passive"))
      (node (ref "USB1") (pin "A9") (pinfunction "VBUS_A9") (pintype "passive"))
      (node (ref "USB1") (pin "B4") (pinfunction "VBUS_B4") (pintype "passive"))
      (node (ref "USB1") (pin "B9") (pinfunction "VBUS_B9") (pintype "passive"))
    )
    (net (code "79") (name "VCC3V3") (class "Default")
      (node (ref "C10") (pin "2") (pinfunction "2_2") (pintype "passive"))
      (node (ref "C11") (pin "2") (pinfunction "2_2") (pintype "passive"))
      (node (ref "C17") (pin "2") (pinfunction "2_2") (pintype "passive"))
      (node (ref "C18") (pin "2") (pinfunction "2_2") (pintype "passive"))
      (node (ref "C5") (pin "2") (pinfunction "2_2") (pintype "passive"))
      (node (ref "C6") (pin "2") (pinfunction "2_2") (pintype "passive"))
      (node (ref "C7") (pin "2") (pinfunction "2_2") (pintype "passive"))
      (node (ref "C8") (pin "2") (pinfunction "2_2") (pintype "passive"))
      (node (ref "F1") (pin "2") (pinfunction "2_2") (pintype "passive"))
      (node (ref "P1") (pin "1") (pinfunction "1_1") (pintype "passive"))
      (node (ref "P2") (pin "1") (pinfunction "1_1") (pintype "passive"))
      (node (ref "P6") (pin "1") (pinfunction "1_1") (pintype "passive"))
      (node (ref "P7") (pin "1") (pinfunction "1_1") (pintype "passive"))
      (node (ref "R1") (pin "1") (pinfunction "1_1") (pintype "passive"))
      (node (ref "R17") (pin "1") (pinfunction "1_1") (pintype "passive"))
      (node (ref "R19") (pin "1") (pinfunction "1_1") (pintype "passive"))
      (node (ref "R2") (pin "1") (pinfunction "1_1") (pintype "passive"))
      (node (ref "R3") (pin "1") (pinfunction "1_1") (pintype "passive"))
      (node (ref "R5") (pin "1") (pinfunction "1_1") (pintype "passive"))
      (node (ref "R6") (pin "1") (pinfunction "1_1") (pintype "passive"))
      (node (ref "R7") (pin "1") (pinfunction "1_1") (pintype "passive"))
      (node (ref "R8") (pin "1") (pinfunction "1_1") (pintype "passive"))
      (node (ref "RST2") (pin "1") (pinfunction "1_1") (pintype "passive"))
      (node (ref "U1") (pin "1") (pinfunction "VBAT_1") (pintype "passive"))
      (node (ref "U1") (pin "19") (pinfunction "VDD_19") (pintype "passive"))
      (node (ref "U1") (pin "32") (pinfunction "VDD_32") (pintype "passive"))
      (node (ref "U1") (pin "48") (pinfunction "VDD_48") (pintype "passive"))
      (node (ref "U1") (pin "64") (pinfunction "VDD_64") (pintype "passive"))
      (node (ref "U2") (pin "5") (pinfunction "VOUT_5") (pintype "passive"))
    )
    (net (code "80") (name "unconnected-(J1-Vref-Pad5)") (class "Default")
      (node (ref "J1") (pin "5") (pinfunction "Vref_5") (pintype "passive+no_connect"))
    )
    (net (code "81") (name "unconnected-(P1-PadMP1)") (class "Default")
      (node (ref "P1") (pin "MP1") (pinfunction "MP1_MP1") (pintype "passive+no_connect"))
    )
    (net (code "82") (name "unconnected-(P1-PadMP2)") (class "Default")
      (node (ref "P1") (pin "MP2") (pinfunction "MP2_MP2") (pintype "passive+no_connect"))
    )
    (net (code "83") (name "unconnected-(P2-PadMP1)") (class "Default")
      (node (ref "P2") (pin "MP1") (pinfunction "MP1_MP1") (pintype "passive+no_connect"))
    )
    (net (code "84") (name "unconnected-(P2-PadMP2)") (class "Default")
      (node (ref "P2") (pin "MP2") (pinfunction "MP2_MP2") (pintype "passive+no_connect"))
    )
    (net (code "85") (name "unconnected-(P3-PadMP1)") (class "Default")
      (node (ref "P3") (pin "MP1") (pinfunction "MP1_MP1") (pintype "passive+no_connect"))
    )
    (net (code "86") (name "unconnected-(P3-PadMP2)") (class "Default")
      (node (ref "P3") (pin "MP2") (pinfunction "MP2_MP2") (pintype "passive+no_connect"))
    )
    (net (code "87") (name "unconnected-(P4-PadMP1)") (class "Default")
      (node (ref "P4") (pin "MP1") (pinfunction "MP1_MP1") (pintype "passive+no_connect"))
    )
    (net (code "88") (name "unconnected-(P4-PadMP2)") (class "Default")
      (node (ref "P4") (pin "MP2") (pinfunction "MP2_MP2") (pintype "passive+no_connect"))
    )
    (net (code "89") (name "unconnected-(P5-PadMP1)") (class "Default")
      (node (ref "P5") (pin "MP1") (pinfunction "MP1_MP1") (pintype "passive+no_connect"))
    )
    (net (code "90") (name "unconnected-(P5-PadMP2)") (class "Default")
      (node (ref "P5") (pin "MP2") (pinfunction "MP2_MP2") (pintype "passive+no_connect"))
    )
    (net (code "91") (name "unconnected-(P6-PadMP1)") (class "Default")
      (node (ref "P6") (pin "MP1") (pinfunction "MP1_MP1") (pintype "passive+no_connect"))
    )
    (net (code "92") (name "unconnected-(P6-PadMP2)") (class "Default")
      (node (ref "P6") (pin "MP2") (pinfunction "MP2_MP2") (pintype "passive+no_connect"))
    )
    (net (code "93") (name "unconnected-(P7-PadMP1)") (class "Default")
      (node (ref "P7") (pin "MP1") (pinfunction "MP1_MP1") (pintype "passive+no_connect"))
    )
    (net (code "94") (name "unconnected-(P7-PadMP2)") (class "Default")
      (node (ref "P7") (pin "MP2") (pinfunction "MP2_MP2") (pintype "passive+no_connect"))
    )
    (net (code "95") (name "unconnected-(P8-PadMP1)") (class "Default")
      (node (ref "P8") (pin "MP1") (pinfunction "MP1_MP1") (pintype "passive+no_connect"))
    )
    (net (code "96") (name "unconnected-(P8-PadMP2)") (class "Default")
      (node (ref "P8") (pin "MP2") (pinfunction "MP2_MP2") (pintype "passive+no_connect"))
    )
    (net (code "97") (name "unconnected-(P9-PadMP1)") (class "Default")
      (node (ref "P9") (pin "MP1") (pinfunction "MP1_MP1") (pintype "passive+no_connect"))
    )
    (net (code "98") (name "unconnected-(P9-PadMP2)") (class "Default")
      (node (ref "P9") (pin "MP2") (pinfunction "MP2_MP2") (pintype "passive+no_connect"))
    )
    (net (code "99") (name "unconnected-(U2-NC-Pad4)") (class "Default")
      (node (ref "U2") (pin "4") (pinfunction "NC_4") (pintype "passive+no_connect"))
    )
    (net (code "100") (name "unconnected-(U3-NC-Pad4)") (class "Default")
      (node (ref "U3") (pin "4") (pinfunction "NC_4") (pintype "passive+no_connect"))
    )
    (net (code "101") (name "unconnected-(USB1-CC1-PadA5)") (class "Default")
      (node (ref "USB1") (pin "A5") (pinfunction "CC1_A5") (pintype "passive+no_connect"))
    )
    (net (code "102") (name "unconnected-(USB1-CC2-PadB5)") (class "Default")
      (node (ref "USB1") (pin "B5") (pinfunction "CC2_B5") (pintype "passive+no_connect"))
    )
    (net (code "103") (name "unconnected-(USB1-RX1+-PadB11)") (class "Default")
      (node (ref "USB1") (pin "B11") (pinfunction "RX1+_B11") (pintype "passive+no_connect"))
    )
    (net (code "104") (name "unconnected-(USB1-RX1--PadB10)") (class "Default")
      (node (ref "USB1") (pin "B10") (pinfunction "RX1-_B10") (pintype "passive+no_connect"))
    )
    (net (code "105") (name "unconnected-(USB1-RX2+-PadA11)") (class "Default")
      (node (ref "USB1") (pin "A11") (pinfunction "RX2+_A11") (pintype "passive+no_connect"))
    )
    (net (code "106") (name "unconnected-(USB1-RX2--PadA10)") (class "Default")
      (node (ref "USB1") (pin "A10") (pinfunction "RX2-_A10") (pintype "passive+no_connect"))
    )
    (net (code "107") (name "unconnected-(USB1-SBU1-PadA8)") (class "Default")
      (node (ref "USB1") (pin "A8") (pinfunction "SBU1_A8") (pintype "passive+no_connect"))
    )
    (net (code "108") (name "unconnected-(USB1-SBU2-PadB8)") (class "Default")
      (node (ref "USB1") (pin "B8") (pinfunction "SBU2_B8") (pintype "passive+no_connect"))
    )
    (net (code "109") (name "unconnected-(USB1-SH1-Pad1)") (class "Default")
      (node (ref "USB1") (pin "1") (pinfunction "SH1_1") (pintype "passive+no_connect"))
    )
    (net (code "110") (name "unconnected-(USB1-SH2-Pad2)") (class "Default")
      (node (ref "USB1") (pin "2") (pinfunction "SH2_2") (pintype "passive+no_connect"))
    )
    (net (code "111") (name "unconnected-(USB1-SH3-Pad3)") (class "Default")
      (node (ref "USB1") (pin "3") (pinfunction "SH3_3") (pintype "passive+no_connect"))
    )
    (net (code "112") (name "unconnected-(USB1-SH4-Pad4)") (class "Default")
      (node (ref "USB1") (pin "4") (pinfunction "SH4_4") (pintype "passive+no_connect"))
    )
    (net (code "113") (name "unconnected-(USB1-TX1+-PadA2)") (class "Default")
      (node (ref "USB1") (pin "A2") (pinfunction "TX1+_A2") (pintype "passive+no_connect"))
    )
    (net (code "114") (name "unconnected-(USB1-TX1--PadA3)") (class "Default")
      (node (ref "USB1") (pin "A3") (pinfunction "TX1-_A3") (pintype "passive+no_connect"))
    )
    (net (code "115") (name "unconnected-(USB1-TX2+-PadB2)") (class "Default")
      (node (ref "USB1") (pin "B2") (pinfunction "TX2+_B2") (pintype "passive+no_connect"))
    )
    (net (code "116") (name "unconnected-(USB1-TX2--PadB3)") (class "Default")
      (node (ref "USB1") (pin "B3") (pinfunction "TX2-_B3") (pintype "passive+no_connect"))
    )
  )
)
